# Connectors.net
KiCad netlist of a schematic drawn in Altium Designer
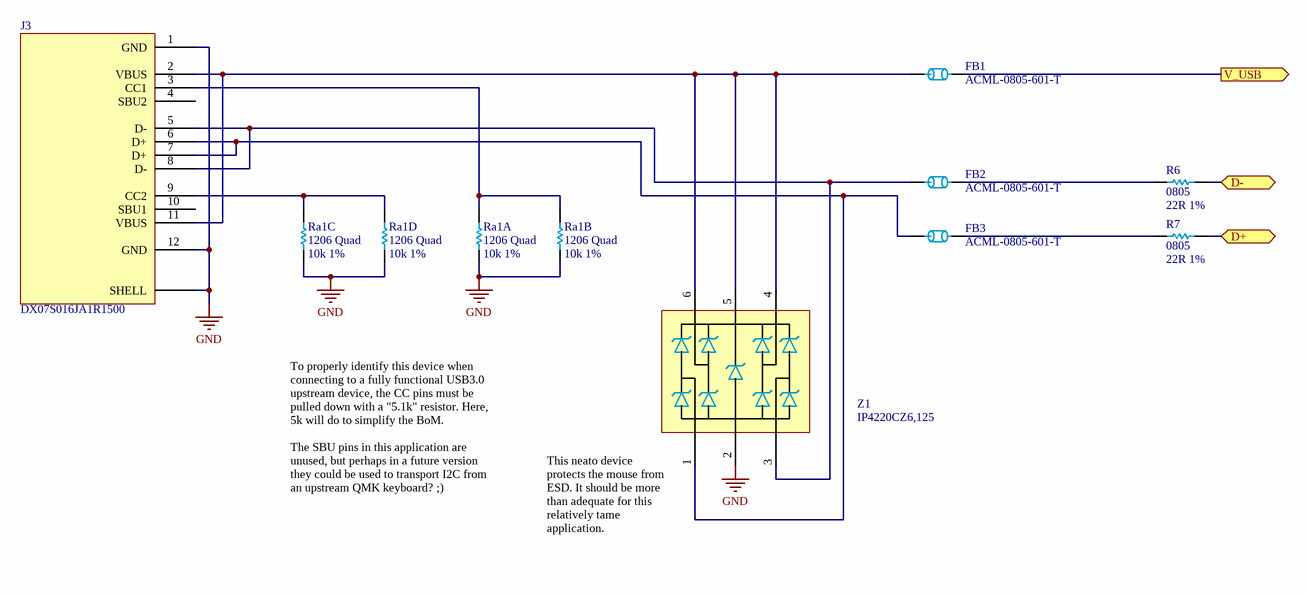
[diagram p0: Connectors.SchDoc]

(export (version "E")
  (design (tool "Eeschema 10.0.6"))
  (components
    (comp (ref "FB1")
      (value "ACML-0805-601-T")
      (footprint "0805")
      (description "FERRITE BEAD 600 OHM 0805 1LN")
      (libsource (lib "Chip_Passives") (part "ACML-0805-601-T"))
    )
    (comp (ref "FB2")
      (value "ACML-0805-601-T")
      (footprint "0805")
      (description "FERRITE BEAD 600 OHM 0805 1LN")
      (libsource (lib "Chip_Passives") (part "ACML-0805-601-T"))
    )
    (comp (ref "FB3")
      (value "ACML-0805-601-T")
      (footprint "0805")
      (description "FERRITE BEAD 600 OHM 0805 1LN")
      (libsource (lib "Chip_Passives") (part "ACML-0805-601-T"))
    )
    (comp (ref "J3")
      (value "DX07S016JA1R1500")
      (footprint "DX07S016JA1R1500")
      (libsource (lib "Connectors") (part "DX07S016JA1R1500"))
    )
    (comp (ref "R6")
      (value "0805")
      (footprint "0805")
      (description "Chip resistor")
      (fields (field (name "ALTIUM_VALUE") "22R 1%"))
      (libsource (lib "Chip_Passives") (part "Res 22R 1% 0805"))
    )
    (comp (ref "R7")
      (value "0805")
      (footprint "0805")
      (description "Chip resistor")
      (fields (field (name "ALTIUM_VALUE") "22R 1%"))
      (libsource (lib "Chip_Passives") (part "Res 22R 1% 0805"))
    )
    (comp (ref "Ra1")
      (value "1206 Quad")
      (footprint "4x 10k 1% - CAC-80P320X160-8M")
      (description "Chip resistor")
      (fields (field (name "ALTIUM_VALUE") "10k 1%"))
      (libsource (lib "Chip_Passives") (part "Quad Res 10k 1% 1206"))
    )
    (comp (ref "Z1")
      (value "IP4220CZ6,125")
      (footprint "PESD3V3S4UD - SOT95P275X110-6N")
      (description "TVS DIODE 5.5V 6TSOP (Low capacitance, USB)")
      (libsource (lib "Diodes") (part "IP4220CZ6,125"))
    )
  )
  (nets
    (net (code "1") (name "/D+") (class "Default")
      (node (ref "R7") (pin "2") (pinfunction "2_2") (pintype "passive"))
    )
    (net (code "2") (name "/D-") (class "Default")
      (node (ref "R6") (pin "2") (pinfunction "2_2") (pintype "passive"))
    )
    (net (code "3") (name "/V_USB") (class "Default")
      (node (ref "FB1") (pin "2") (pinfunction "2_2") (pintype "passive"))
    )
    (net (code "4") (name "GND") (class "Default")
      (node (ref "J3") (pin "1") (pinfunction "GND_1") (pintype "passive"))
      (node (ref "J3") (pin "12") (pinfunction "GND_12") (pintype "passive"))
      (node (ref "J3") (pin "SHELL") (pinfunction "SHELL_SHELL") (pintype "passive"))
      (node (ref "Ra1") (pin "1") (pinfunction "1_1") (pintype "passive"))
      (node (ref "Ra1") (pin "2") (pinfunction "2_2") (pintype "passive"))
      (node (ref "Ra1") (pin "3") (pinfunction "3_3") (pintype "passive"))
      (node (ref "Ra1") (pin "4") (pinfunction "4_4") (pintype "passive"))
      (node (ref "Z1") (pin "2") (pinfunction "2_2") (pintype "passive"))
    )
    (net (code "5") (name "Net-(FB1-Pad1)") (class "Default")
      (node (ref "FB1") (pin "1") (pinfunction "1_1") (pintype "passive"))
      (node (ref "J3") (pin "11") (pinfunction "VBUS_11") (pintype "passive"))
      (node (ref "J3") (pin "2") (pinfunction "VBUS_2") (pintype "passive"))
      (node (ref "Z1") (pin "4") (pinfunction "4_4") (pintype "passive"))
      (node (ref "Z1") (pin "5") (pinfunction "5_5") (pintype "passive"))
      (node (ref "Z1") (pin "6") (pinfunction "6_6") (pintype "passive"))
    )
    (net (code "6") (name "Net-(FB2-Pad1)") (class "Default")
      (node (ref "FB2") (pin "1") (pinfunction "1_1") (pintype "passive"))
      (node (ref "J3") (pin "5") (pinfunction "D-_5") (pintype "passive"))
      (node (ref "J3") (pin "8") (pinfunction "D-_8") (pintype "passive"))
      (node (ref "Z1") (pin "3") (pinfunction "3_3") (pintype "passive"))
    )
    (net (code "7") (name "Net-(FB2-Pad2)") (class "Default")
      (node (ref "FB2") (pin "2") (pinfunction "2_2") (pintype "passive"))
      (node (ref "R6") (pin "1") (pinfunction "1_1") (pintype "passive"))
    )
    (net (code "8") (name "Net-(FB3-Pad1)") (class "Default")
      (node (ref "FB3") (pin "1") (pinfunction "1_1") (pintype "passive"))
      (node (ref "J3") (pin "6") (pinfunction "D+_6") (pintype "passive"))
      (node (ref "J3") (pin "7") (pinfunction "D+_7") (pintype "passive"))
      (node (ref "Z1") (pin "1") (pinfunction "1_1") (pintype "passive"))
    )
    (net (code "9") (name "Net-(FB3-Pad2)") (class "Default")
      (node (ref "FB3") (pin "2") (pinfunction "2_2") (pintype "passive"))
      (node (ref "R7") (pin "1") (pinfunction "1_1") (pintype "passive"))
    )
    (net (code "10") (name "Net-(J3-CC1)") (class "Default")
      (node (ref "J3") (pin "3") (pinfunction "CC1_3") (pintype "passive"))
      (node (ref "Ra1") (pin "7") (pinfunction "7_7") (pintype "passive"))
      (node (ref "Ra1") (pin "8") (pinfunction "8_8") (pintype "passive"))
    )
    (net (code "11") (name "Net-(J3-CC2)") (class "Default")
      (node (ref "J3") (pin "9") (pinfunction "CC2_9") (pintype "passive"))
      (node (ref "Ra1") (pin "5") (pinfunction "5_5") (pintype "passive"))
      (node (ref "Ra1") (pin "6") (pinfunction "6_6") (pintype "passive"))
    )
    (net (code "12") (name "unconnected-(J3-SBU1-Pad10)") (class "Default")
      (node (ref "J3") (pin "10") (pinfunction "SBU1_10") (pintype "passive"))
    )
    (net (code "13") (name "unconnected-(J3-SBU2-Pad4)") (class "Default")
      (node (ref "J3") (pin "4") (pinfunction "SBU2_4") (pintype "passive"))
    )
  )
)
